# what-the-frequency-mk-1.net
KiCad netlist of a schematic drawn in EAGLE
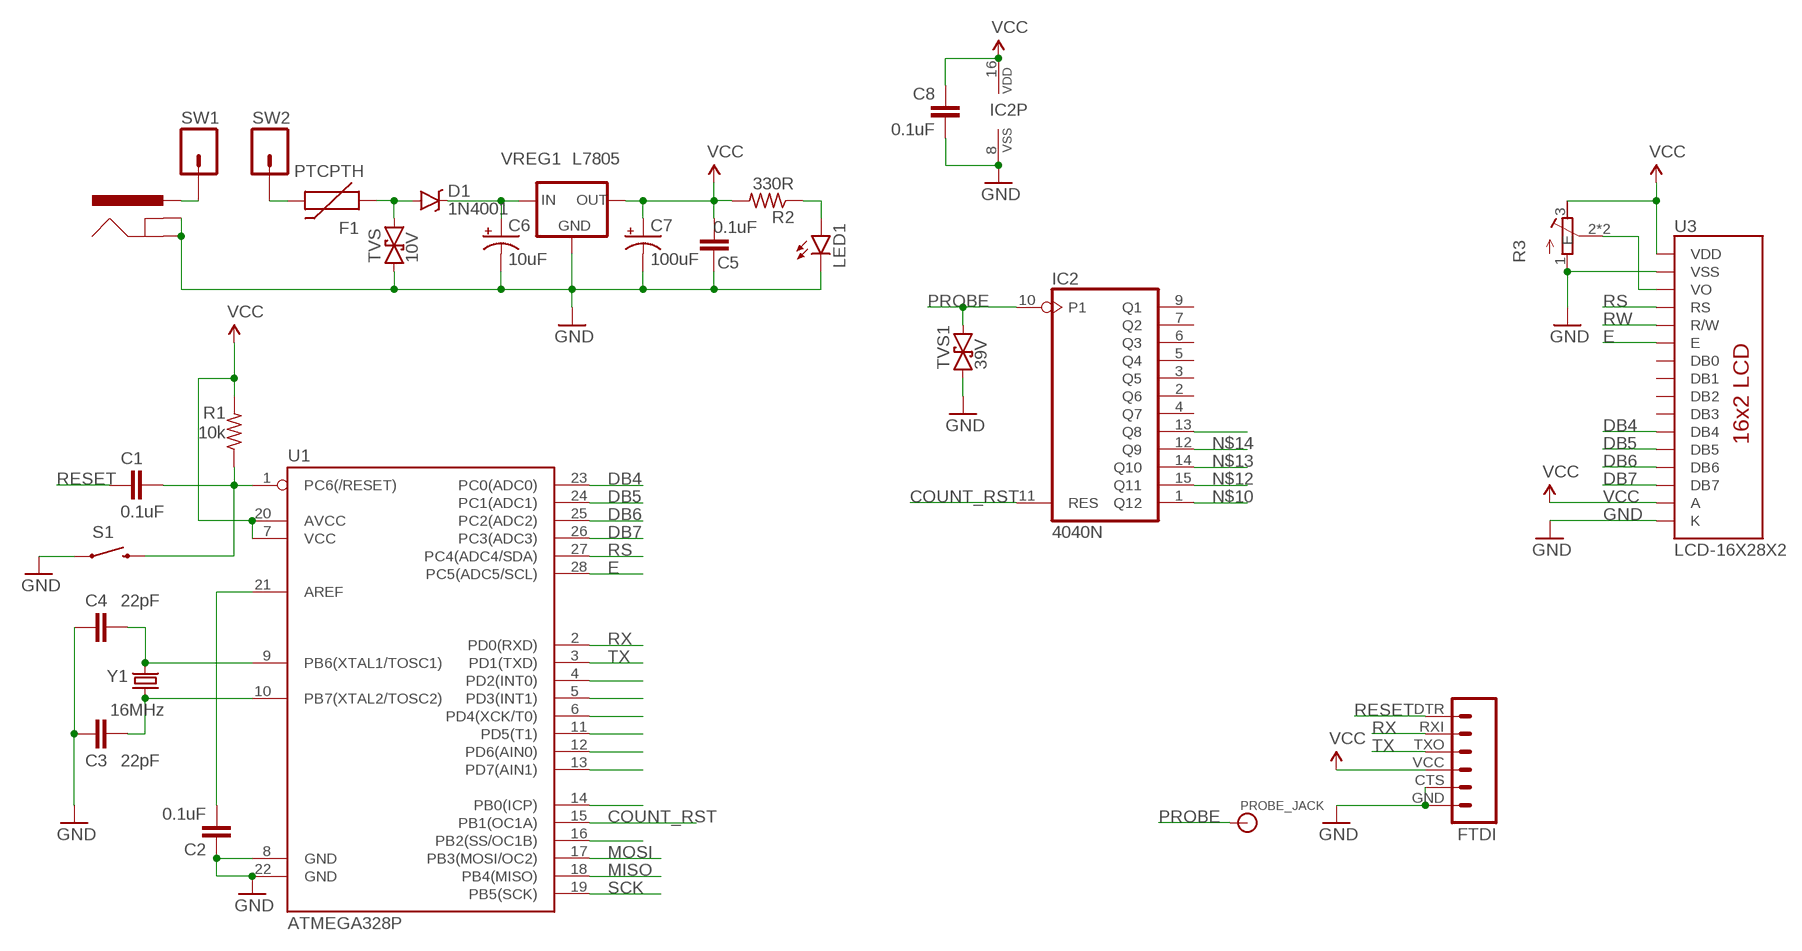
[diagram p0: schematic, sheet 1]

(export (version "E")
  (design (tool "Eeschema 10.0.6"))
  (components
    (comp (ref "C1")
      (value "0.1uF")
      (footprint "eagle-import:C025-024X044")
      (libsource (lib "eagle-import") (part "CAPACITOR-CERAMIC025-024X044"))
    )
    (comp (ref "C2")
      (value "0.1uF")
      (footprint "eagle-import:C025-024X044")
      (libsource (lib "eagle-import") (part "CAPACITOR-CERAMIC025-024X044"))
    )
    (comp (ref "C3")
      (value "22pF")
      (footprint "eagle-import:C025-024X044")
      (libsource (lib "eagle-import") (part "CAPACITOR-CERAMIC025-024X044"))
    )
    (comp (ref "C4")
      (value "22pF")
      (footprint "eagle-import:C025-024X044")
      (libsource (lib "eagle-import") (part "CAPACITOR-CERAMIC025-024X044"))
    )
    (comp (ref "C5")
      (value "0.1uF")
      (footprint "eagle-import:C025-024X044")
      (libsource (lib "eagle-import") (part "CAPACITOR-CERAMIC025-024X044"))
    )
    (comp (ref "C6")
      (value "10uF")
      (footprint "eagle-import:E2,5-5")
      (libsource (lib "eagle-import") (part "CAPACITOR-POLARIZEDE2.5-5"))
    )
    (comp (ref "C7")
      (value "100uF")
      (footprint "eagle-import:E2,5-5")
      (libsource (lib "eagle-import") (part "CAPACITOR-POLARIZEDE2.5-5"))
    )
    (comp (ref "C8")
      (value "0.1uF")
      (footprint "eagle-import:C025-024X044")
      (libsource (lib "eagle-import") (part "CAPACITOR-CERAMIC025-024X044"))
    )
    (comp (ref "D1")
      (value "1N4001")
      (footprint "eagle-import:DO-41")
      (libsource (lib "eagle-import") (part "DIODE-SCHOTTKYDO-41"))
    )
    (comp (ref "F1")
      (value "PTCPTH")
      (footprint "eagle-import:PTC")
      (libsource (lib "eagle-import") (part "PTCPTH"))
    )
    (comp (ref "FTDI")
      (value "FTDI_BASICPTH-TINY-TEXT")
      (footprint "eagle-import:FTDI_TINY_TXT")
      (libsource (lib "eagle-import") (part "FTDI_BASICPTH-TINY-TEXT"))
    )
    (comp (ref "IC2")
      (value "4040N")
      (footprint "eagle-import:DIL16")
      (libsource (lib "eagle-import") (part "4040N"))
    )
    (comp (ref "J2")
      (value "POWER_JACKPTH")
      (footprint "eagle-import:POWER_JACK_PTH")
      (libsource (lib "eagle-import") (part "POWER_JACKPTH"))
    )
    (comp (ref "LED1")
      (value "LED3MM")
      (footprint "eagle-import:LED3MM")
      (libsource (lib "eagle-import") (part "LED3MM"))
    )
    (comp (ref "PROBE_JACK")
      (value "BANANA_CONNPTH-RA")
      (footprint "eagle-import:BANANA-PTH-RA-SAFEWORD")
      (libsource (lib "eagle-import") (part "BANANA_CONNPTH-RA"))
    )
    (comp (ref "R1")
      (value "10k")
      (footprint "eagle-import:AXIAL-PTH-5.08MM")
      (libsource (lib "eagle-import") (part "RESISTORPTH-AXIAL-5.08MM"))
    )
    (comp (ref "R2")
      (value "330R")
      (footprint "eagle-import:AXIAL-PTH-5.08MM")
      (libsource (lib "eagle-import") (part "RESISTORPTH-AXIAL-5.08MM"))
    )
    (comp (ref "R3")
      (value "POTENTIOMETERTHUMBWHEEL-16MM")
      (footprint "eagle-import:POT-THUMBWHEEL")
      (libsource (lib "eagle-import") (part "POTENTIOMETERTHUMBWHEEL-16MM"))
    )
    (comp (ref "S1")
      (value "SWITCH-MOMENTARY-2PTH-RA")
      (footprint "eagle-import:TACTILE-PTH-SIDE")
      (libsource (lib "eagle-import") (part "SWITCH-MOMENTARY-2PTH-RA"))
    )
    (comp (ref "SW1")
      (value "M01PTH_2MM")
      (footprint "eagle-import:1X01_2MM")
      (libsource (lib "eagle-import") (part "M01PTH_2MM"))
    )
    (comp (ref "SW2")
      (value "M01PTH_2MM")
      (footprint "eagle-import:1X01_2MM")
      (libsource (lib "eagle-import") (part "M01PTH_2MM"))
    )
    (comp (ref "TVS")
      (value "10V")
      (footprint "eagle-import:DO-41-TVS")
      (libsource (lib "eagle-import") (part "TVSDO-41-TVS-BIDIRECTIONAL"))
    )
    (comp (ref "TVS1")
      (value "39V")
      (footprint "eagle-import:DO-41-TVS")
      (libsource (lib "eagle-import") (part "TVSDO-41-TVS-BIDIRECTIONAL"))
    )
    (comp (ref "U1")
      (value "ATMEGA328P")
      (footprint "eagle-import:DIL28-3")
      (libsource (lib "eagle-import") (part "ATMEGA328P_PDIP"))
    )
    (comp (ref "U3")
      (value "LCD-16X28X2")
      (footprint "eagle-import:LCD-8X2")
      (libsource (lib "eagle-import") (part "LCD-16X28X2"))
    )
    (comp (ref "VREG1")
      (value "L7805")
      (footprint "eagle-import:TO-92-AMMO")
      (libsource (lib "eagle-import") (part "V_REG_78XXTO-92-INLINE"))
    )
    (comp (ref "Y1")
      (value "16MHz")
      (footprint "eagle-import:HC49U-V")
      (libsource (lib "eagle-import") (part "CRYSTALHC49UV"))
    )
  )
  (nets
    (net (code "1") (name "/COUNT_RST") (class "Default")
      (node (ref "IC2") (pin "11") (pinfunction "RES_11") (pintype "input"))
      (node (ref "U1") (pin "15") (pinfunction "PB1(OC1A)_15") (pintype "bidirectional"))
    )
    (net (code "2") (name "/DB4") (class "Default")
      (node (ref "U1") (pin "23") (pinfunction "PC0(ADC0)_23") (pintype "bidirectional"))
      (node (ref "U3") (pin "11") (pinfunction "DB4_11") (pintype "bidirectional"))
    )
    (net (code "3") (name "/DB5") (class "Default")
      (node (ref "U1") (pin "24") (pinfunction "PC1(ADC1)_24") (pintype "bidirectional"))
      (node (ref "U3") (pin "12") (pinfunction "DB5_12") (pintype "bidirectional"))
    )
    (net (code "4") (name "/DB6") (class "Default")
      (node (ref "U1") (pin "25") (pinfunction "PC2(ADC2)_25") (pintype "bidirectional"))
      (node (ref "U3") (pin "13") (pinfunction "DB6_13") (pintype "bidirectional"))
    )
    (net (code "5") (name "/DB7") (class "Default")
      (node (ref "U1") (pin "26") (pinfunction "PC3(ADC3)_26") (pintype "bidirectional"))
      (node (ref "U3") (pin "14") (pinfunction "DB7_14") (pintype "bidirectional"))
    )
    (net (code "6") (name "/E") (class "Default")
      (node (ref "U1") (pin "28") (pinfunction "PC5(ADC5/SCL)_28") (pintype "bidirectional"))
      (node (ref "U3") (pin "6") (pinfunction "E_6") (pintype "input"))
    )
    (net (code "7") (name "/MISO") (class "Default")
      (node (ref "U1") (pin "18") (pinfunction "PB4(MISO)_18") (pintype "bidirectional"))
    )
    (net (code "8") (name "/MOSI") (class "Default")
      (node (ref "U1") (pin "17") (pinfunction "PB3(MOSI/OC2)_17") (pintype "bidirectional"))
    )
    (net (code "9") (name "/N$10") (class "Default")
      (node (ref "IC2") (pin "1") (pinfunction "Q12_1") (pintype "output"))
    )
    (net (code "10") (name "/N$12") (class "Default")
      (node (ref "IC2") (pin "15") (pinfunction "Q11_15") (pintype "output"))
    )
    (net (code "11") (name "/N$13") (class "Default")
      (node (ref "IC2") (pin "14") (pinfunction "Q10_14") (pintype "output"))
    )
    (net (code "12") (name "/N$14") (class "Default")
      (node (ref "IC2") (pin "12") (pinfunction "Q9_12") (pintype "output"))
    )
    (net (code "13") (name "/PROBE") (class "Default")
      (node (ref "IC2") (pin "10") (pinfunction "P1_10") (pintype "input"))
      (node (ref "PROBE_JACK") (pin "P$1") (pinfunction "1_P$1") (pintype "passive"))
      (node (ref "PROBE_JACK") (pin "P$2") (pinfunction "1_P$2") (pintype "passive"))
      (node (ref "TVS1") (pin "P$2") (pinfunction "2_P$2") (pintype "passive"))
    )
    (net (code "14") (name "/RESET") (class "Default")
      (node (ref "C1") (pin "1") (pinfunction "1_1") (pintype "passive"))
      (node (ref "FTDI") (pin "DTR") (pinfunction "1_DTR") (pintype "passive"))
    )
    (net (code "15") (name "/RS") (class "Default")
      (node (ref "U1") (pin "27") (pinfunction "PC4(ADC4/SDA)_27") (pintype "bidirectional"))
      (node (ref "U3") (pin "4") (pinfunction "RS_4") (pintype "input"))
    )
    (net (code "16") (name "/RW") (class "Default")
      (node (ref "U3") (pin "5") (pinfunction "R/W_5") (pintype "input"))
    )
    (net (code "17") (name "/RX") (class "Default")
      (node (ref "FTDI") (pin "RXI") (pinfunction "2_RXI") (pintype "passive"))
      (node (ref "U1") (pin "2") (pinfunction "PD0(RXD)_2") (pintype "bidirectional"))
    )
    (net (code "18") (name "/SCK") (class "Default")
      (node (ref "U1") (pin "19") (pinfunction "PB5(SCK)_19") (pintype "bidirectional"))
    )
    (net (code "19") (name "/TX") (class "Default")
      (node (ref "FTDI") (pin "TXO") (pinfunction "3_TXO") (pintype "passive"))
      (node (ref "U1") (pin "3") (pinfunction "PD1(TXD)_3") (pintype "bidirectional"))
    )
    (net (code "20") (name "GND") (class "Default")
      (node (ref "C2") (pin "1") (pinfunction "1_1") (pintype "passive"))
      (node (ref "C3") (pin "2") (pinfunction "2_2") (pintype "passive"))
      (node (ref "C4") (pin "2") (pinfunction "2_2") (pintype "passive"))
      (node (ref "C5") (pin "1") (pinfunction "1_1") (pintype "passive"))
      (node (ref "C6") (pin "-") (pinfunction "-_-") (pintype "passive"))
      (node (ref "C7") (pin "-") (pinfunction "-_-") (pintype "passive"))
      (node (ref "C8") (pin "1") (pinfunction "1_1") (pintype "passive"))
      (node (ref "FTDI") (pin "CTS") (pinfunction "5_CTS") (pintype "passive"))
      (node (ref "FTDI") (pin "GND") (pinfunction "6_GND") (pintype "passive"))
      (node (ref "IC2") (pin "8") (pinfunction "VSS_8") (pintype "power_in"))
      (node (ref "J2") (pin "GND") (pinfunction "GND_GND") (pintype "bidirectional"))
      (node (ref "J2") (pin "GNDBREAK") (pinfunction "GNDBREAK_GNDBREAK") (pintype "bidirectional"))
      (node (ref "LED1") (pin "K") (pinfunction "C_K") (pintype "passive"))
      (node (ref "R3") (pin "1") (pinfunction "A_1") (pintype "passive"))
      (node (ref "S1") (pin "1") (pinfunction "1_1") (pintype "passive"))
      (node (ref "TVS") (pin "P$1") (pinfunction "1_P$1") (pintype "passive"))
      (node (ref "TVS1") (pin "P$1") (pinfunction "1_P$1") (pintype "passive"))
      (node (ref "U1") (pin "22") (pinfunction "GND_22") (pintype "bidirectional"))
      (node (ref "U1") (pin "8") (pinfunction "GND_8") (pintype "bidirectional"))
      (node (ref "U3") (pin "1") (pinfunction "VSS_1") (pintype "power_in"))
      (node (ref "U3") (pin "16") (pinfunction "K_16") (pintype "power_in"))
      (node (ref "VREG1") (pin "2") (pinfunction "GND_2") (pintype "input"))
    )
    (net (code "21") (name "Net-(F1-1)") (class "Default")
      (node (ref "D1") (pin "A") (pinfunction "A_A") (pintype "passive"))
      (node (ref "F1") (pin "P$1") (pinfunction "1_P$1") (pintype "bidirectional"))
      (node (ref "TVS") (pin "P$2") (pinfunction "2_P$2") (pintype "passive"))
    )
    (net (code "22") (name "Net-(F1-2)") (class "Default")
      (node (ref "F1") (pin "P$2") (pinfunction "2_P$2") (pintype "bidirectional"))
      (node (ref "SW2") (pin "1") (pinfunction "1_1") (pintype "passive"))
    )
    (net (code "23") (name "Net-(J2-PadPWR)") (class "Default")
      (node (ref "J2") (pin "PWR") (pinfunction "PWR_PWR") (pintype "bidirectional"))
      (node (ref "SW1") (pin "1") (pinfunction "1_1") (pintype "passive"))
    )
    (net (code "24") (name "Net-(R1-1)") (class "Default")
      (node (ref "C1") (pin "2") (pinfunction "2_2") (pintype "passive"))
      (node (ref "R1") (pin "P$1") (pinfunction "1_P$1") (pintype "passive"))
      (node (ref "S1") (pin "2") (pinfunction "2_2") (pintype "passive"))
      (node (ref "U1") (pin "1") (pinfunction "PC6(/RESET)_1") (pintype "bidirectional"))
    )
    (net (code "25") (name "Net-(R2-1)") (class "Default")
      (node (ref "LED1") (pin "A") (pinfunction "A_A") (pintype "passive"))
      (node (ref "R2") (pin "P$1") (pinfunction "1_P$1") (pintype "passive"))
    )
    (net (code "26") (name "Net-(U1-AREF)") (class "Default")
      (node (ref "C2") (pin "2") (pinfunction "2_2") (pintype "passive"))
      (node (ref "U1") (pin "21") (pinfunction "AREF_21") (pintype "bidirectional"))
    )
    (net (code "27") (name "Net-(U1-PB6(XTAL1{slash}TOSC1))") (class "Default")
      (node (ref "C4") (pin "1") (pinfunction "1_1") (pintype "passive"))
      (node (ref "U1") (pin "9") (pinfunction "PB6(XTAL1/TOSC1)_9") (pintype "bidirectional"))
      (node (ref "Y1") (pin "2") (pinfunction "2_2") (pintype "passive"))
    )
    (net (code "28") (name "Net-(U1-PB7(XTAL2{slash}TOSC2))") (class "Default")
      (node (ref "C3") (pin "1") (pinfunction "1_1") (pintype "passive"))
      (node (ref "U1") (pin "10") (pinfunction "PB7(XTAL2/TOSC2)_10") (pintype "bidirectional"))
      (node (ref "Y1") (pin "1") (pinfunction "1_1") (pintype "passive"))
    )
    (net (code "29") (name "Net-(U3-VO)") (class "Default")
      (node (ref "R3") (pin "2") (pinfunction "S_2") (pintype "passive"))
      (node (ref "R3") (pin "2@1") (pinfunction "S_2@1") (pintype "passive"))
      (node (ref "U3") (pin "3") (pinfunction "VO_3") (pintype "bidirectional"))
    )
    (net (code "30") (name "Net-(VREG1-IN)") (class "Default")
      (node (ref "C6") (pin "+") (pinfunction "+_+") (pintype "passive"))
      (node (ref "D1") (pin "C") (pinfunction "C_C") (pintype "passive"))
      (node (ref "VREG1") (pin "1") (pinfunction "IN_1") (pintype "input"))
    )
    (net (code "31") (name "VCC") (class "Default")
      (node (ref "C5") (pin "2") (pinfunction "2_2") (pintype "passive"))
      (node (ref "C7") (pin "+") (pinfunction "+_+") (pintype "passive"))
      (node (ref "C8") (pin "2") (pinfunction "2_2") (pintype "passive"))
      (node (ref "FTDI") (pin "VCC") (pinfunction "4_VCC") (pintype "passive"))
      (node (ref "IC2") (pin "16") (pinfunction "VDD_16") (pintype "power_in"))
      (node (ref "R1") (pin "P$2") (pinfunction "2_P$2") (pintype "passive"))
      (node (ref "R2") (pin "P$2") (pinfunction "2_P$2") (pintype "passive"))
      (node (ref "R3") (pin "3") (pinfunction "E_3") (pintype "passive"))
      (node (ref "U1") (pin "20") (pinfunction "AVCC_20") (pintype "bidirectional"))
      (node (ref "U1") (pin "7") (pinfunction "VCC_7") (pintype "bidirectional"))
      (node (ref "U3") (pin "15") (pinfunction "A_15") (pintype "power_in"))
      (node (ref "U3") (pin "2") (pinfunction "VDD_2") (pintype "power_in"))
      (node (ref "VREG1") (pin "3") (pinfunction "OUT_3") (pintype "output"))
    )
    (net (code "32") (name "unconnected-(IC2A-Q1-Pad9)") (class "Default")
      (node (ref "IC2") (pin "9") (pinfunction "Q1_9") (pintype "output"))
    )
    (net (code "33") (name "unconnected-(IC2A-Q2-Pad7)") (class "Default")
      (node (ref "IC2") (pin "7") (pinfunction "Q2_7") (pintype "output"))
    )
    (net (code "34") (name "unconnected-(IC2A-Q3-Pad6)") (class "Default")
      (node (ref "IC2") (pin "6") (pinfunction "Q3_6") (pintype "output"))
    )
    (net (code "35") (name "unconnected-(IC2A-Q4-Pad5)") (class "Default")
      (node (ref "IC2") (pin "5") (pinfunction "Q4_5") (pintype "output"))
    )
    (net (code "36") (name "unconnected-(IC2A-Q5-Pad3)") (class "Default")
      (node (ref "IC2") (pin "3") (pinfunction "Q5_3") (pintype "output"))
    )
    (net (code "37") (name "unconnected-(IC2A-Q6-Pad2)") (class "Default")
      (node (ref "IC2") (pin "2") (pinfunction "Q6_2") (pintype "output"))
    )
    (net (code "38") (name "unconnected-(IC2A-Q7-Pad4)") (class "Default")
      (node (ref "IC2") (pin "4") (pinfunction "Q7_4") (pintype "output"))
    )
    (net (code "39") (name "unconnected-(IC2A-Q8-Pad13)") (class "Default")
      (node (ref "IC2") (pin "13") (pinfunction "Q8_13") (pintype "output"))
    )
    (net (code "40") (name "unconnected-(U1-PB0(ICP)-Pad14)") (class "Default")
      (node (ref "U1") (pin "14") (pinfunction "PB0(ICP)_14") (pintype "bidirectional"))
    )
    (net (code "41") (name "unconnected-(U1-PB2(SS{slash}OC1B)-Pad16)") (class "Default")
      (node (ref "U1") (pin "16") (pinfunction "PB2(SS/OC1B)_16") (pintype "bidirectional"))
    )
    (net (code "42") (name "unconnected-(U1-PD2(INT0)-Pad4)") (class "Default")
      (node (ref "U1") (pin "4") (pinfunction "PD2(INT0)_4") (pintype "bidirectional"))
    )
    (net (code "43") (name "unconnected-(U1-PD3(INT1)-Pad5)") (class "Default")
      (node (ref "U1") (pin "5") (pinfunction "PD3(INT1)_5") (pintype "bidirectional"))
    )
    (net (code "44") (name "unconnected-(U1-PD4(XCK{slash}T0)-Pad6)") (class "Default")
      (node (ref "U1") (pin "6") (pinfunction "PD4(XCK/T0)_6") (pintype "bidirectional"))
    )
    (net (code "45") (name "unconnected-(U1-PD5(T1)-Pad11)") (class "Default")
      (node (ref "U1") (pin "11") (pinfunction "PD5(T1)_11") (pintype "bidirectional"))
    )
    (net (code "46") (name "unconnected-(U1-PD6(AIN0)-Pad12)") (class "Default")
      (node (ref "U1") (pin "12") (pinfunction "PD6(AIN0)_12") (pintype "bidirectional"))
    )
    (net (code "47") (name "unconnected-(U1-PD7(AIN1)-Pad13)") (class "Default")
      (node (ref "U1") (pin "13") (pinfunction "PD7(AIN1)_13") (pintype "bidirectional"))
    )
    (net (code "48") (name "unconnected-(U3-DB0-Pad7)") (class "Default")
      (node (ref "U3") (pin "7") (pinfunction "DB0_7") (pintype "bidirectional"))
    )
    (net (code "49") (name "unconnected-(U3-DB1-Pad8)") (class "Default")
      (node (ref "U3") (pin "8") (pinfunction "DB1_8") (pintype "bidirectional"))
    )
    (net (code "50") (name "unconnected-(U3-DB2-Pad9)") (class "Default")
      (node (ref "U3") (pin "9") (pinfunction "DB2_9") (pintype "bidirectional"))
    )
    (net (code "51") (name "unconnected-(U3-DB3-Pad10)") (class "Default")
      (node (ref "U3") (pin "10") (pinfunction "DB3_10") (pintype "bidirectional"))
    )
  )
)
